# ADL5536-SCH.net
KiCad netlist of a schematic drawn in Altium Designer
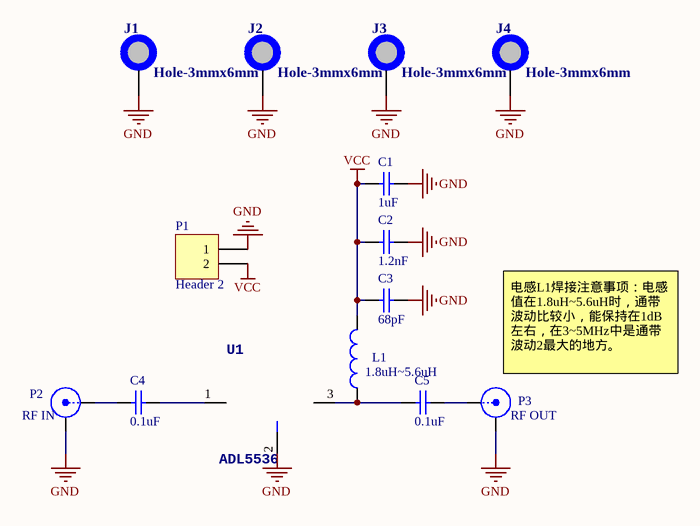
[diagram p0: ADL5536-SCH.SchDoc]

(export (version "E")
  (design (tool "Eeschema 10.0.6"))
  (components
    (comp (ref "C1")
      (value "1uF")
      (footprint "1206C")
      (description "CAP CER 10000PF 100V X7R 0603")
      (fields
        (field (name "MANUFACTURER") "TDK Corporation")
        (field (name "MANUFACTURER PART NUMBER") "C1608X7R2A103K080AA")
      )
      (libsource (lib "Desiger_Schlib") (part "Cap1"))
    )
    (comp (ref "C2")
      (value "1.2nF")
      (footprint "0603C")
      (description "CAP CER 10000PF 100V X7R 0603")
      (fields
        (field (name "MANUFACTURER") "TDK Corporation")
        (field (name "MANUFACTURER PART NUMBER") "C1608X7R2A103K080AA")
      )
      (libsource (lib "Desiger_Schlib") (part "Cap1"))
    )
    (comp (ref "C3")
      (value "68pF")
      (footprint "0603C")
      (description "CAP CER 10000PF 100V X7R 0603")
      (fields
        (field (name "MANUFACTURER") "TDK Corporation")
        (field (name "MANUFACTURER PART NUMBER") "C1608X7R2A103K080AA")
      )
      (libsource (lib "Desiger_Schlib") (part "Cap1"))
    )
    (comp (ref "C4")
      (value "0.1uF")
      (footprint "0603C")
      (description "CAP CER 10000PF 100V X7R 0603")
      (fields
        (field (name "MANUFACTURER") "TDK Corporation")
        (field (name "MANUFACTURER PART NUMBER") "C1608X7R2A103K080AA")
      )
      (libsource (lib "Desiger_Schlib") (part "Cap1"))
    )
    (comp (ref "C5")
      (value "0.1uF")
      (footprint "0603C")
      (description "CAP CER 10000PF 100V X7R 0603")
      (fields
        (field (name "MANUFACTURER") "TDK Corporation")
        (field (name "MANUFACTURER PART NUMBER") "C1608X7R2A103K080AA")
      )
      (libsource (lib "Desiger_Schlib") (part "Cap1"))
    )
    (comp (ref "J1")
      (value "Hole-3mmx6mm")
      (footprint "Hole")
      (libsource (lib "Desiger_Schlib") (part "HOLED"))
    )
    (comp (ref "J2")
      (value "Hole-3mmx6mm")
      (footprint "Hole")
      (libsource (lib "Desiger_Schlib") (part "HOLED"))
    )
    (comp (ref "J3")
      (value "Hole-3mmx6mm")
      (footprint "Hole")
      (libsource (lib "Desiger_Schlib") (part "HOLED"))
    )
    (comp (ref "J4")
      (value "Hole-3mmx6mm")
      (footprint "Hole")
      (libsource (lib "Desiger_Schlib") (part "HOLED"))
    )
    (comp (ref "L1")
      (value "1.8uH~5.6uH")
      (footprint "0805L")
      (description "FIXED IND 240NH 4.4A 22MOHM SMD")
      (fields
        (field (name "MANUFACTURER") "Samsung Electro-Mechanics")
        (field (name "MANUFACTURER PART NUMBER") "CIGT201210UHR24MNE")
      )
      (libsource (lib "Desiger_Schlib") (part "Inductors"))
    )
    (comp (ref "P1")
      (value "Header 2")
      (footprint "KF2EDG_3R81_2P")
      (description "Header, 2-Pin")
      (fields (field (name "PUBLISHER") "Altium Limited"))
      (libsource (lib "Miscellaneous Connectors") (part "Header 2"))
    )
    (comp (ref "P2")
      (value "RF IN")
      (footprint "SMA-SMD")
      (description "BNC Elbow Connector")
      (fields (field (name "PUBLISHER") "Altium Limited"))
      (libsource (lib "Miscellaneous Connectors") (part "BNC"))
    )
    (comp (ref "P3")
      (value "RF OUT")
      (footprint "SMA-SMD")
      (description "BNC Elbow Connector")
      (fields (field (name "PUBLISHER") "Altium Limited"))
      (libsource (lib "Miscellaneous Connectors") (part "BNC"))
    )
    (comp (ref "U1")
      (value "ADL5536")
      (footprint "SOT89")
      (description "Medium Power, High Linearity Amplifier")
      (libsource (lib "Desiger_Schlib") (part "ADL5536"))
    )
  )
  (nets
    (net (code "1") (name "GND") (class "Default")
      (node (ref "C1") (pin "2") (pinfunction "2_2") (pintype "passive"))
      (node (ref "C2") (pin "2") (pinfunction "2_2") (pintype "passive"))
      (node (ref "C3") (pin "2") (pinfunction "2_2") (pintype "passive"))
      (node (ref "J1") (pin "0") (pinfunction "0_0") (pintype "passive"))
      (node (ref "J2") (pin "0") (pinfunction "0_0") (pintype "passive"))
      (node (ref "J3") (pin "0") (pinfunction "0_0") (pintype "passive"))
      (node (ref "J4") (pin "0") (pinfunction "0_0") (pintype "passive"))
      (node (ref "P1") (pin "1") (pinfunction "1_1") (pintype "passive"))
      (node (ref "P2") (pin "2") (pinfunction "Y_2") (pintype "passive"))
      (node (ref "P3") (pin "2") (pinfunction "Y_2") (pintype "passive"))
      (node (ref "U1") (pin "2") (pinfunction "GND_2") (pintype "passive"))
    )
    (net (code "2") (name "Net-(P2-X)") (class "Default")
      (node (ref "C4") (pin "1") (pinfunction "1_1") (pintype "passive"))
      (node (ref "P2") (pin "1") (pinfunction "X_1") (pintype "passive"))
    )
    (net (code "3") (name "Net-(P3-X)") (class "Default")
      (node (ref "C5") (pin "2") (pinfunction "2_2") (pintype "passive"))
      (node (ref "P3") (pin "1") (pinfunction "X_1") (pintype "passive"))
    )
    (net (code "4") (name "Net-(U1-RF_IN)") (class "Default")
      (node (ref "C4") (pin "2") (pinfunction "2_2") (pintype "passive"))
      (node (ref "U1") (pin "1") (pinfunction "RF_IN_1") (pintype "passive"))
    )
    (net (code "5") (name "Net-(U1-RF_OUT)") (class "Default")
      (node (ref "C5") (pin "1") (pinfunction "1_1") (pintype "passive"))
      (node (ref "L1") (pin "1") (pinfunction "1_1") (pintype "passive"))
      (node (ref "U1") (pin "3") (pinfunction "RF_OUT_3") (pintype "passive"))
    )
    (net (code "6") (name "VCC") (class "Default")
      (node (ref "C1") (pin "1") (pinfunction "1_1") (pintype "passive"))
      (node (ref "C2") (pin "1") (pinfunction "1_1") (pintype "passive"))
      (node (ref "C3") (pin "1") (pinfunction "1_1") (pintype "passive"))
      (node (ref "L1") (pin "2") (pinfunction "2_2") (pintype "passive"))
      (node (ref "P1") (pin "2") (pinfunction "2_2") (pintype "passive"))
    )
  )
)
